# Light_Control_-_6ports.net
KiCad netlist of a schematic drawn in Altium Designer
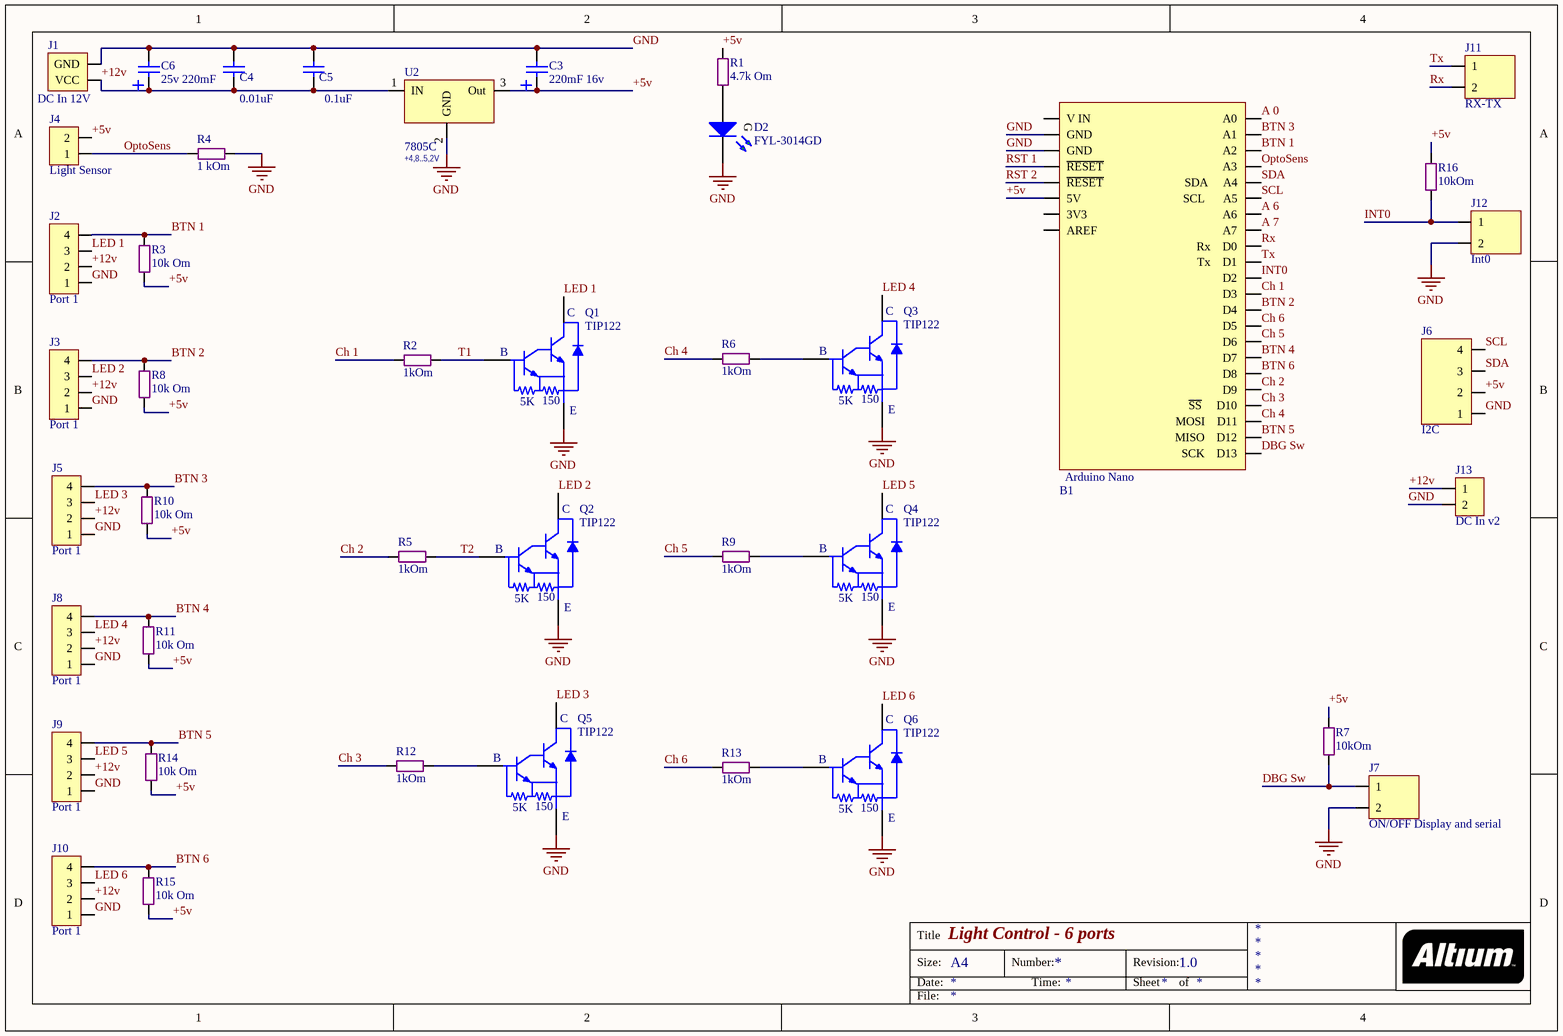
[diagram p0: Light Control - 6ports.SchDoc]

(export (version "E")
  (design (tool "Eeschema 10.0.6"))
  (components
    (comp (ref "B1")
      (value "Arduino Nano")
      (footprint "Boards:Arduino Nano v3")
      (libsource (lib "Boards") (part "Arduino Nano"))
    )
    (comp (ref "C3")
      (value "220mF 16v")
      (footprint "Capacitor:Cap E p2mm D6.5xH11")
      (description "Capacitor")
      (libsource (lib "Capacitor") (part "Cap E 220mF x 16V"))
    )
    (comp (ref "C4")
      (value "0.01uF")
      (footprint "Capacitor:SMD 0805 (2012)")
      (description "Capacitor")
      (libsource (lib "Capacitor") (part "Cap SMD 0402-1812"))
    )
    (comp (ref "C5")
      (value "0.1uF")
      (footprint "Capacitor:SMD 0805 (2012)")
      (description "Capacitor")
      (libsource (lib "Capacitor") (part "Cap SMD 0402-1812"))
    )
    (comp (ref "C6")
      (value "25v 220mF")
      (footprint "Capacitor:Cap E p2mm D6.5xH11")
      (description "Capacitor")
      (libsource (lib "Capacitor") (part "Cap E 220mF x 16V"))
    )
    (comp (ref "D2")
      (value "FYL-3014GD")
      (footprint "LED:LED Round 3mm Green")
      (description "2.1v 10mA, 15-30mCd")
      (libsource (lib "LED") (part "Led Round 3mm Green"))
    )
    (comp (ref "J1")
      (value "DC In 12V")
      (footprint "Connector:DC Connector")
      (description "DC Connector")
      (libsource (lib "Connector") (part "DC Connector (PJ-002B)"))
    )
    (comp (ref "J2")
      (value "Port 1")
      (footprint "Connector:Molex Micro-Fit 3.0 - 4 pin D R")
      (description "Horisontal, Dbl line, Male - 3mm")
      (fields (field (name "PART NUMBER") "0430450402"))
      (libsource (lib "Connector") (part "Micro-Fit 4R (2x2)"))
    )
    (comp (ref "J3")
      (value "Port 1")
      (footprint "Connector:Molex Micro-Fit 3.0 - 4 pin D R")
      (description "Horisontal, Dbl line, Male - 3mm")
      (fields (field (name "PART NUMBER") "0430450402"))
      (libsource (lib "Connector") (part "Micro-Fit 4R (2x2)"))
    )
    (comp (ref "J4")
      (value "Light Sensor")
      (footprint "Connector:Molex Micro-Fit 3.0 - 2 pin D R")
      (description "Horisontal, Dbl line, Male - 3mm")
      (fields (field (name "PART NUMBER") "430450200"))
      (libsource (lib "Connector") (part "Micro-Fit 2R (1x2)"))
    )
    (comp (ref "J5")
      (value "Port 1")
      (footprint "Connector:Molex Micro-Fit 3.0 - 4 pin D R")
      (description "Horisontal, Dbl line, Male - 3mm")
      (fields (field (name "PART NUMBER") "0430450402"))
      (libsource (lib "Connector") (part "Micro-Fit 4R (2x2)"))
    )
    (comp (ref "J6")
      (value "I2C")
      (footprint "Connector:Line 2.54 X 4")
      (description "Vert, Sgl line, Male")
      (libsource (lib "Connector") (part "PLS-4"))
    )
    (comp (ref "J7")
      (value "ON/OFF Display and serial")
      (footprint "Connector:Line 2.54 x 2")
      (description "Vert, Sgl line, Male")
      (libsource (lib "Connector") (part "PLS-2"))
    )
    (comp (ref "J8")
      (value "Port 1")
      (footprint "Connector:Molex Micro-Fit 3.0 - 4 pin D R")
      (description "Horisontal, Dbl line, Male - 3mm")
      (fields (field (name "PART NUMBER") "0430450402"))
      (libsource (lib "Connector") (part "Micro-Fit 4R (2x2)"))
    )
    (comp (ref "J9")
      (value "Port 1")
      (footprint "Connector:Molex Micro-Fit 3.0 - 4 pin D R")
      (description "Horisontal, Dbl line, Male - 3mm")
      (fields (field (name "PART NUMBER") "0430450402"))
      (libsource (lib "Connector") (part "Micro-Fit 4R (2x2)"))
    )
    (comp (ref "J10")
      (value "Port 1")
      (footprint "Connector:Molex Micro-Fit 3.0 - 4 pin D R")
      (description "Horisontal, Dbl line, Male - 3mm")
      (fields (field (name "PART NUMBER") "0430450402"))
      (libsource (lib "Connector") (part "Micro-Fit 4R (2x2)"))
    )
    (comp (ref "J11")
      (value "RX-TX")
      (footprint "Connector:Line 2.54 x 2")
      (description "Vert, Sgl line, Male")
      (libsource (lib "Connector") (part "PLS-2"))
    )
    (comp (ref "J12")
      (value "Int0")
      (footprint "Connector:Line 2.54 x 2")
      (description "Vert, Sgl line, Male")
      (libsource (lib "Connector") (part "PLS-2"))
    )
    (comp (ref "J13")
      (value "DC In v2")
      (footprint "Connector:DG301 5mm 2p")
      (description "DG301 series")
      (libsource (lib "Connector") (part "DG301-5.0-2P12"))
    )
    (comp (ref "Q1")
      (value "TIP122")
      (footprint "GeneralCases:TO220-2")
      (description "NPN Darlington 5A, 65W, 100V, h>1000")
      (libsource (lib "Transistor") (part "TIP122"))
    )
    (comp (ref "Q2")
      (value "TIP122")
      (footprint "GeneralCases:TO220-2")
      (description "NPN Darlington 5A, 65W, 100V, h>1000")
      (libsource (lib "Transistor") (part "TIP122"))
    )
    (comp (ref "Q3")
      (value "TIP122")
      (footprint "GeneralCases:TO220-2")
      (description "NPN Darlington 5A, 65W, 100V, h>1000")
      (libsource (lib "Transistor") (part "TIP122"))
    )
    (comp (ref "Q4")
      (value "TIP122")
      (footprint "GeneralCases:TO220-2")
      (description "NPN Darlington 5A, 65W, 100V, h>1000")
      (libsource (lib "Transistor") (part "TIP122"))
    )
    (comp (ref "Q5")
      (value "TIP122")
      (footprint "GeneralCases:TO220-2")
      (description "NPN Darlington 5A, 65W, 100V, h>1000")
      (libsource (lib "Transistor") (part "TIP122"))
    )
    (comp (ref "Q6")
      (value "TIP122")
      (footprint "GeneralCases:TO220-2")
      (description "NPN Darlington 5A, 65W, 100V, h>1000")
      (libsource (lib "Transistor") (part "TIP122"))
    )
    (comp (ref "R1")
      (value "4.7k Om")
      (footprint "PassiveComponents:SMD 0805 (2012)")
      (libsource (lib "PassiveComponents") (part "Res All Types"))
    )
    (comp (ref "R2")
      (value "1kOm")
      (footprint "PassiveComponents:SMD 1206 (3216)")
      (libsource (lib "PassiveComponents") (part "Res All Types"))
    )
    (comp (ref "R3")
      (value "10k Om")
      (footprint "PassiveComponents:Res p7.62 (4p) 0.25w")
      (libsource (lib "PassiveComponents") (part "Res All Types"))
    )
    (comp (ref "R4")
      (value "1 kOm")
      (footprint "PassiveComponents:SMD 0805 (2012)")
      (libsource (lib "PassiveComponents") (part "Res All Types"))
    )
    (comp (ref "R5")
      (value "1kOm")
      (footprint "PassiveComponents:SMD 0805 (2012)")
      (libsource (lib "PassiveComponents") (part "Res All Types"))
    )
    (comp (ref "R6")
      (value "1kOm")
      (footprint "PassiveComponents:SMD 0805 (2012)")
      (libsource (lib "PassiveComponents") (part "Res All Types"))
    )
    (comp (ref "R7")
      (value "10kOm")
      (footprint "PassiveComponents:SMD 0805 (2012)")
      (libsource (lib "PassiveComponents") (part "Res All Types"))
    )
    (comp (ref "R8")
      (value "10k Om")
      (footprint "PassiveComponents:SMD 0805 (2012)")
      (libsource (lib "PassiveComponents") (part "Res All Types"))
    )
    (comp (ref "R9")
      (value "1kOm")
      (footprint "PassiveComponents:SMD 0805 (2012)")
      (libsource (lib "PassiveComponents") (part "Res All Types"))
    )
    (comp (ref "R10")
      (value "10k Om")
      (footprint "PassiveComponents:SMD 0805 (2012)")
      (libsource (lib "PassiveComponents") (part "Res All Types"))
    )
    (comp (ref "R11")
      (value "10k Om")
      (footprint "PassiveComponents:Res p7.62 (4p) 0.25w")
      (libsource (lib "PassiveComponents") (part "Res All Types"))
    )
    (comp (ref "R12")
      (value "1kOm")
      (footprint "PassiveComponents:SMD 0805 (2012)")
      (libsource (lib "PassiveComponents") (part "Res All Types"))
    )
    (comp (ref "R13")
      (value "1kOm")
      (footprint "PassiveComponents:SMD 0805 (2012)")
      (libsource (lib "PassiveComponents") (part "Res All Types"))
    )
    (comp (ref "R14")
      (value "10k Om")
      (footprint "PassiveComponents:Res p7.62 (4p) 0.25w")
      (libsource (lib "PassiveComponents") (part "Res All Types"))
    )
    (comp (ref "R15")
      (value "10k Om")
      (footprint "PassiveComponents:Res p7.62 (4p) 0.25w")
      (libsource (lib "PassiveComponents") (part "Res All Types"))
    )
    (comp (ref "R16")
      (value "10kOm")
      (footprint "PassiveComponents:SMD 0805 (2012)")
      (libsource (lib "PassiveComponents") (part "Res All Types"))
    )
    (comp (ref "U2")
      (value "7805C")
      (footprint "GeneralCases:D-PAK")
      (description "Voltage Regulator")
      (fields (field (name "MANUFACTURER") "Интеграл") (field (name "V OUT") "+4,8..5,2V"))
      (libsource (lib "PowerAdjusment") (part "7805C"))
    )
  )
  (nets
    (net (code "1") (name "/+5v") (class "Default")
      (node (ref "B1") (pin "5V") (pinfunction "5V_5V") (pintype "passive"))
      (node (ref "C3") (pin "1") (pinfunction "1_1") (pintype "passive"))
      (node (ref "J4") (pin "2") (pinfunction "2_2") (pintype "passive"))
      (node (ref "J6") (pin "2") (pinfunction "2_2") (pintype "passive"))
      (node (ref "R1") (pin "1") (pinfunction "1_1") (pintype "passive"))
      (node (ref "R10") (pin "2") (pinfunction "2_2") (pintype "passive"))
      (node (ref "R11") (pin "2") (pinfunction "2_2") (pintype "passive"))
      (node (ref "R14") (pin "2") (pinfunction "2_2") (pintype "passive"))
      (node (ref "R15") (pin "2") (pinfunction "2_2") (pintype "passive"))
      (node (ref "R16") (pin "2") (pinfunction "2_2") (pintype "passive"))
      (node (ref "R3") (pin "2") (pinfunction "2_2") (pintype "passive"))
      (node (ref "R7") (pin "2") (pinfunction "2_2") (pintype "passive"))
      (node (ref "R8") (pin "2") (pinfunction "2_2") (pintype "passive"))
      (node (ref "U2") (pin "3") (pinfunction "Out_3") (pintype "power_in"))
    )
    (net (code "2") (name "/+12v") (class "Default")
      (node (ref "C4") (pin "2") (pinfunction "2_2") (pintype "passive"))
      (node (ref "C5") (pin "2") (pinfunction "2_2") (pintype "passive"))
      (node (ref "C6") (pin "1") (pinfunction "1_1") (pintype "passive"))
      (node (ref "J1") (pin "VCC") (pinfunction "VCC_VCC") (pintype "passive"))
      (node (ref "J10") (pin "2") (pinfunction "2_2") (pintype "passive"))
      (node (ref "J13") (pin "1") (pinfunction "1_1") (pintype "passive"))
      (node (ref "J2") (pin "2") (pinfunction "2_2") (pintype "passive"))
      (node (ref "J3") (pin "2") (pinfunction "2_2") (pintype "passive"))
      (node (ref "J5") (pin "2") (pinfunction "2_2") (pintype "passive"))
      (node (ref "J8") (pin "2") (pinfunction "2_2") (pintype "passive"))
      (node (ref "J9") (pin "2") (pinfunction "2_2") (pintype "passive"))
      (node (ref "U2") (pin "1") (pinfunction "IN_1") (pintype "power_in"))
    )
    (net (code "3") (name "/A 0") (class "Default")
      (node (ref "B1") (pin "A0") (pinfunction "A0_A0") (pintype "passive"))
    )
    (net (code "4") (name "/A 6") (class "Default")
      (node (ref "B1") (pin "A6") (pinfunction "A6_A6") (pintype "passive"))
    )
    (net (code "5") (name "/A 7") (class "Default")
      (node (ref "B1") (pin "A7") (pinfunction "A7_A7") (pintype "passive"))
    )
    (net (code "6") (name "/BTN 1") (class "Default")
      (node (ref "B1") (pin "A2") (pinfunction "A2_A2") (pintype "passive"))
      (node (ref "J2") (pin "4") (pinfunction "4_4") (pintype "passive"))
      (node (ref "R3") (pin "1") (pinfunction "1_1") (pintype "passive"))
    )
    (net (code "7") (name "/BTN 2") (class "Default")
      (node (ref "B1") (pin "D4") (pinfunction "D4_D4") (pintype "passive"))
      (node (ref "J3") (pin "4") (pinfunction "4_4") (pintype "passive"))
      (node (ref "R8") (pin "1") (pinfunction "1_1") (pintype "passive"))
    )
    (net (code "8") (name "/BTN 3") (class "Default")
      (node (ref "B1") (pin "A1") (pinfunction "A1_A1") (pintype "passive"))
      (node (ref "J5") (pin "4") (pinfunction "4_4") (pintype "passive"))
      (node (ref "R10") (pin "1") (pinfunction "1_1") (pintype "passive"))
    )
    (net (code "9") (name "/BTN 4") (class "Default")
      (node (ref "B1") (pin "D7") (pinfunction "D7_D7") (pintype "passive"))
      (node (ref "J8") (pin "4") (pinfunction "4_4") (pintype "passive"))
      (node (ref "R11") (pin "1") (pinfunction "1_1") (pintype "passive"))
    )
    (net (code "10") (name "/BTN 5") (class "Default")
      (node (ref "B1") (pin "D12") (pinfunction "MISO____D12_D12") (pintype "passive"))
      (node (ref "J9") (pin "4") (pinfunction "4_4") (pintype "passive"))
      (node (ref "R14") (pin "1") (pinfunction "1_1") (pintype "passive"))
    )
    (net (code "11") (name "/BTN 6") (class "Default")
      (node (ref "B1") (pin "D8") (pinfunction "D8_D8") (pintype "passive"))
      (node (ref "J10") (pin "4") (pinfunction "4_4") (pintype "passive"))
      (node (ref "R15") (pin "1") (pinfunction "1_1") (pintype "passive"))
    )
    (net (code "12") (name "/Ch 1") (class "Default")
      (node (ref "B1") (pin "D3") (pinfunction "D3_D3") (pintype "passive"))
      (node (ref "R2") (pin "1") (pinfunction "1_1") (pintype "passive"))
    )
    (net (code "13") (name "/Ch 2") (class "Default")
      (node (ref "B1") (pin "D9") (pinfunction "D9_D9") (pintype "passive"))
      (node (ref "R5") (pin "1") (pinfunction "1_1") (pintype "passive"))
    )
    (net (code "14") (name "/Ch 3") (class "Default")
      (node (ref "B1") (pin "D10") (pinfunction "~{SS}_____D10_D10") (pintype "passive"))
      (node (ref "R12") (pin "1") (pinfunction "1_1") (pintype "passive"))
    )
    (net (code "15") (name "/Ch 4") (class "Default")
      (node (ref "B1") (pin "D11") (pinfunction "MOSI____D11_D11") (pintype "passive"))
      (node (ref "R6") (pin "1") (pinfunction "1_1") (pintype "passive"))
    )
    (net (code "16") (name "/Ch 5") (class "Default")
      (node (ref "B1") (pin "D6") (pinfunction "D6_D6") (pintype "passive"))
      (node (ref "R9") (pin "1") (pinfunction "1_1") (pintype "passive"))
    )
    (net (code "17") (name "/Ch 6") (class "Default")
      (node (ref "B1") (pin "D5") (pinfunction "D5_D5") (pintype "passive"))
      (node (ref "R13") (pin "1") (pinfunction "1_1") (pintype "passive"))
    )
    (net (code "18") (name "/DBG Sw") (class "Default")
      (node (ref "B1") (pin "D13") (pinfunction "SCK____D13_D13") (pintype "passive"))
      (node (ref "J7") (pin "1") (pinfunction "1_1") (pintype "passive"))
      (node (ref "R7") (pin "1") (pinfunction "1_1") (pintype "passive"))
    )
    (net (code "19") (name "/INT0") (class "Default")
      (node (ref "B1") (pin "D2") (pinfunction "D2_D2") (pintype "passive"))
      (node (ref "J12") (pin "1") (pinfunction "1_1") (pintype "passive"))
      (node (ref "R16") (pin "1") (pinfunction "1_1") (pintype "passive"))
    )
    (net (code "20") (name "/LED 1") (class "Default")
      (node (ref "J2") (pin "3") (pinfunction "3_3") (pintype "passive"))
      (node (ref "Q1") (pin "2") (pinfunction "C_2") (pintype "passive"))
    )
    (net (code "21") (name "/LED 2") (class "Default")
      (node (ref "J3") (pin "3") (pinfunction "3_3") (pintype "passive"))
      (node (ref "Q2") (pin "2") (pinfunction "C_2") (pintype "passive"))
    )
    (net (code "22") (name "/LED 3") (class "Default")
      (node (ref "J5") (pin "3") (pinfunction "3_3") (pintype "passive"))
      (node (ref "Q5") (pin "2") (pinfunction "C_2") (pintype "passive"))
    )
    (net (code "23") (name "/LED 4") (class "Default")
      (node (ref "J8") (pin "3") (pinfunction "3_3") (pintype "passive"))
      (node (ref "Q3") (pin "2") (pinfunction "C_2") (pintype "passive"))
    )
    (net (code "24") (name "/LED 5") (class "Default")
      (node (ref "J9") (pin "3") (pinfunction "3_3") (pintype "passive"))
      (node (ref "Q4") (pin "2") (pinfunction "C_2") (pintype "passive"))
    )
    (net (code "25") (name "/LED 6") (class "Default")
      (node (ref "J10") (pin "3") (pinfunction "3_3") (pintype "passive"))
      (node (ref "Q6") (pin "2") (pinfunction "C_2") (pintype "passive"))
    )
    (net (code "26") (name "/OptoSens") (class "Default")
      (node (ref "B1") (pin "A3") (pinfunction "A3_A3") (pintype "passive"))
      (node (ref "J4") (pin "1") (pinfunction "1_1") (pintype "passive"))
      (node (ref "R4") (pin "1") (pinfunction "1_1") (pintype "passive"))
    )
    (net (code "27") (name "/RST 1") (class "Default")
      (node (ref "B1") (pin "Rst1") (pinfunction "~{RESET}_Rst1") (pintype "passive"))
    )
    (net (code "28") (name "/RST 2") (class "Default")
      (node (ref "B1") (pin "Rst2") (pinfunction "~{RESET}_Rst2") (pintype "passive"))
    )
    (net (code "29") (name "/Rx") (class "Default")
      (node (ref "B1") (pin "D0") (pinfunction "Rx____D0_D0") (pintype "passive"))
      (node (ref "J11") (pin "2") (pinfunction "2_2") (pintype "passive"))
    )
    (net (code "30") (name "/SCL") (class "Default")
      (node (ref "B1") (pin "A5") (pinfunction "SCL______A5_A5") (pintype "passive"))
      (node (ref "J6") (pin "4") (pinfunction "4_4") (pintype "passive"))
    )
    (net (code "31") (name "/SDA") (class "Default")
      (node (ref "B1") (pin "A4") (pinfunction "SDA_____A4_A4") (pintype "passive"))
      (node (ref "J6") (pin "3") (pinfunction "3_3") (pintype "passive"))
    )
    (net (code "32") (name "/T1") (class "Default")
      (node (ref "Q1") (pin "1") (pinfunction "B_1") (pintype "passive"))
      (node (ref "R2") (pin "2") (pinfunction "2_2") (pintype "passive"))
    )
    (net (code "33") (name "/T2") (class "Default")
      (node (ref "Q2") (pin "1") (pinfunction "B_1") (pintype "passive"))
      (node (ref "R5") (pin "2") (pinfunction "2_2") (pintype "passive"))
    )
    (net (code "34") (name "/Tx") (class "Default")
      (node (ref "B1") (pin "D1") (pinfunction "Tx____D1_D1") (pintype "passive"))
      (node (ref "J11") (pin "1") (pinfunction "1_1") (pintype "passive"))
    )
    (net (code "35") (name "GND") (class "Default")
      (node (ref "B1") (pin "Gnd1") (pinfunction "GND_Gnd1") (pintype "passive"))
      (node (ref "B1") (pin "Gnd2") (pinfunction "GND_Gnd2") (pintype "passive"))
      (node (ref "C3") (pin "2") (pinfunction "2_2") (pintype "passive"))
      (node (ref "C4") (pin "1") (pinfunction "1_1") (pintype "passive"))
      (node (ref "C5") (pin "1") (pinfunction "1_1") (pintype "passive"))
      (node (ref "C6") (pin "2") (pinfunction "2_2") (pintype "passive"))
      (node (ref "D2") (pin "K") (pinfunction "K_K") (pintype "passive"))
      (node (ref "J1") (pin "GND") (pinfunction "GND_GND") (pintype "passive"))
      (node (ref "J10") (pin "1") (pinfunction "1_1") (pintype "passive"))
      (node (ref "J12") (pin "2") (pinfunction "2_2") (pintype "passive"))
      (node (ref "J13") (pin "2") (pinfunction "2_2") (pintype "passive"))
      (node (ref "J2") (pin "1") (pinfunction "1_1") (pintype "passive"))
      (node (ref "J3") (pin "1") (pinfunction "1_1") (pintype "passive"))
      (node (ref "J5") (pin "1") (pinfunction "1_1") (pintype "passive"))
      (node (ref "J6") (pin "1") (pinfunction "1_1") (pintype "passive"))
      (node (ref "J7") (pin "2") (pinfunction "2_2") (pintype "passive"))
      (node (ref "J8") (pin "1") (pinfunction "1_1") (pintype "passive"))
      (node (ref "J9") (pin "1") (pinfunction "1_1") (pintype "passive"))
      (node (ref "Q1") (pin "3") (pinfunction "E_3") (pintype "passive"))
      (node (ref "Q2") (pin "3") (pinfunction "E_3") (pintype "passive"))
      (node (ref "Q3") (pin "3") (pinfunction "E_3") (pintype "passive"))
      (node (ref "Q4") (pin "3") (pinfunction "E_3") (pintype "passive"))
      (node (ref "Q5") (pin "3") (pinfunction "E_3") (pintype "passive"))
      (node (ref "Q6") (pin "3") (pinfunction "E_3") (pintype "passive"))
      (node (ref "R4") (pin "2") (pinfunction "2_2") (pintype "passive"))
      (node (ref "U2") (pin "2") (pinfunction "GND_2") (pintype "passive"))
    )
    (net (code "36") (name "Net-(D2-PadA)") (class "Default")
      (node (ref "D2") (pin "A") (pinfunction "A_A") (pintype "passive"))
      (node (ref "R1") (pin "2") (pinfunction "2_2") (pintype "passive"))
    )
    (net (code "37") (name "Net-(Q3-B)") (class "Default")
      (node (ref "Q3") (pin "1") (pinfunction "B_1") (pintype "passive"))
      (node (ref "R6") (pin "2") (pinfunction "2_2") (pintype "passive"))
    )
    (net (code "38") (name "Net-(Q4-B)") (class "Default")
      (node (ref "Q4") (pin "1") (pinfunction "B_1") (pintype "passive"))
      (node (ref "R9") (pin "2") (pinfunction "2_2") (pintype "passive"))
    )
    (net (code "39") (name "Net-(Q5-B)") (class "Default")
      (node (ref "Q5") (pin "1") (pinfunction "B_1") (pintype "passive"))
      (node (ref "R12") (pin "2") (pinfunction "2_2") (pintype "passive"))
    )
    (net (code "40") (name "Net-(Q6-B)") (class "Default")
      (node (ref "Q6") (pin "1") (pinfunction "B_1") (pintype "passive"))
      (node (ref "R13") (pin "2") (pinfunction "2_2") (pintype "passive"))
    )
    (net (code "41") (name "unconnected-(B1-AREF-PadAref)") (class "Default")
      (node (ref "B1") (pin "Aref") (pinfunction "AREF_Aref") (pintype "passive"))
    )
    (net (code "42") (name "unconnected-(B1-Pad3V3)") (class "Default")
      (node (ref "B1") (pin "3V3") (pinfunction "3V3_3V3") (pintype "passive"))
    )
    (net (code "43") (name "unconnected-(B1-V_IN-PadVin)") (class "Default")
      (node (ref "B1") (pin "Vin") (pinfunction "V_IN_Vin") (pintype "power_in"))
    )
  )
)
